# tunnelAmp.net
KiCad netlist of a schematic drawn in Altium Designer
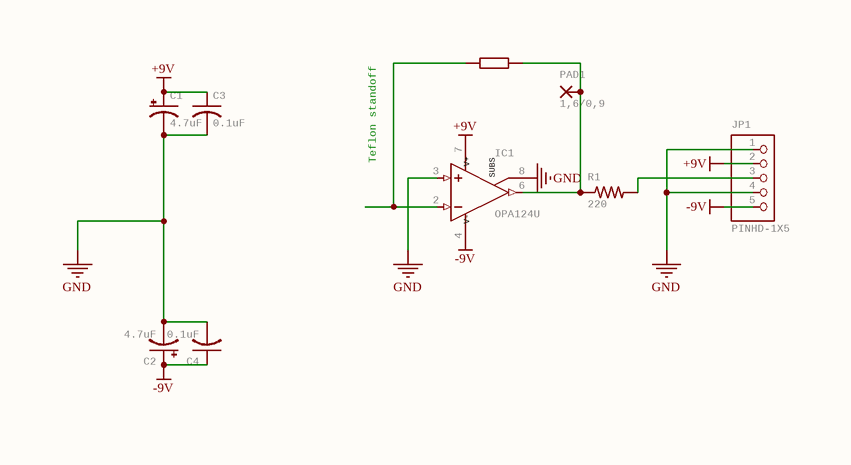
[diagram p0: tunnelAmp.SchDoc]

(export (version "E")
  (design (tool "Eeschema 10.0.6"))
  (components
    (comp (ref "C1")
      (value "4.7uF")
      (footprint "C/6032-28W")
      (description "POLARIZED CAPACITOR, American symbol")
      (libsource (lib "") (part "CPOL-USC/6032-28W_1"))
    )
    (comp (ref "C2")
      (value "4.7uF")
      (footprint "C/6032-28W")
      (description "POLARIZED CAPACITOR, American symbol")
      (libsource (lib "resistor") (part "CPOL-USC/6032-28W"))
    )
    (comp (ref "C3")
      (value "0.1uF")
      (footprint "C0603")
      (description "CAPACITOR, American symbol")
      (libsource (lib "resistor") (part "C-USC0603"))
    )
    (comp (ref "C4")
      (value "0.1uF")
      (footprint "C0603")
      (description "CAPACITOR, American symbol")
      (libsource (lib "resistor") (part "C-USC0603"))
    )
    (comp (ref "IC1")
      (value "OPA124U")
      (footprint "SO08")
      (description "Difet Operational Amplifier")
      (fields
        (field (name "V+") "V+")
        (field (name "V-") "V-")
        (field (name "SUBS") "SUBS")
        (field (name "LIBRARYNAME") "burr-brown")
      )
      (libsource (lib "burr-brown") (part "OPA124U"))
    )
    (comp (ref "JP1")
      (value "PINHD-1X5")
      (footprint "1X05")
      (description "PIN HEADER")
      (fields (field (name "LIBRARYNAME") "pinhead"))
      (libsource (lib "pinhead") (part "PINHD-1X5"))
    )
    (comp (ref "PAD1")
      (value "1,6/0,9")
      (footprint "1,6/0,9")
      (description "THROUGH-HOLE PAD")
      (fields (field (name "LIBRARYNAME") "wirepad"))
      (libsource (lib "wirepad") (part "1,6/0,9"))
    )
    (comp (ref "R1")
      (value "220")
      (footprint "R0603")
      (description "RESISTOR, American symbol")
      (libsource (lib "resistor") (part "R-US_R0603"))
    )
    (comp (ref "R3")
      (value "100M")
      (description "RESISTOR")
      (fields (field (name "LIBRARYNAME") "docu-dummy"))
      (libsource (lib "docu-dummy") (part "R"))
    )
  )
  (nets
    (net (code "1") (name "+9V") (class "Default")
      (node (ref "C1") (pin "+") (pinfunction "+_+") (pintype "passive"))
      (node (ref "C3") (pin "1") (pinfunction "1_1") (pintype "passive"))
      (node (ref "IC1") (pin "7") (pinfunction "V+_7") (pintype "power_in"))
      (node (ref "JP1") (pin "2") (pinfunction "2_2") (pintype "passive"))
    )
    (net (code "2") (name "-9V") (class "Default")
      (node (ref "C2") (pin "+") (pinfunction "+_+") (pintype "passive"))
      (node (ref "C4") (pin "1") (pinfunction "1_1") (pintype "passive"))
      (node (ref "IC1") (pin "4") (pinfunction "V-_4") (pintype "power_in"))
      (node (ref "JP1") (pin "5") (pinfunction "5_5") (pintype "passive"))
    )
    (net (code "3") (name "GND") (class "Default")
      (node (ref "C1") (pin "-") (pinfunction "-_-") (pintype "passive"))
      (node (ref "C2") (pin "-") (pinfunction "-_-") (pintype "passive"))
      (node (ref "C3") (pin "2") (pinfunction "2_2") (pintype "passive"))
      (node (ref "C4") (pin "2") (pinfunction "2_2") (pintype "passive"))
      (node (ref "IC1") (pin "3") (pinfunction "+IN_3") (pintype "input"))
      (node (ref "IC1") (pin "8") (pinfunction "SUBS_8") (pintype "passive"))
      (node (ref "JP1") (pin "1") (pinfunction "1_1") (pintype "passive"))
      (node (ref "JP1") (pin "4") (pinfunction "4_4") (pintype "passive"))
    )
    (net (code "4") (name "Net-(IC1-OUT)") (class "Default")
      (node (ref "IC1") (pin "6") (pinfunction "OUT_6") (pintype "output"))
      (node (ref "PAD1") (pin "1") (pinfunction "P_1") (pintype "passive"))
      (node (ref "R1") (pin "1") (pinfunction "1_1") (pintype "passive"))
    )
    (net (code "5") (name "Net-(JP1-Pad3)") (class "Default")
      (node (ref "JP1") (pin "3") (pinfunction "3_3") (pintype "passive"))
      (node (ref "R1") (pin "2") (pinfunction "2_2") (pintype "passive"))
    )
    (net (code "6") (name "unconnected-(IC1--IN-Pad2)") (class "Default")
      (node (ref "IC1") (pin "2") (pinfunction "-IN_2") (pintype "input"))
    )
  )
)
